# SmartPlantSensor.net
KiCad netlist of a schematic drawn in EAGLE
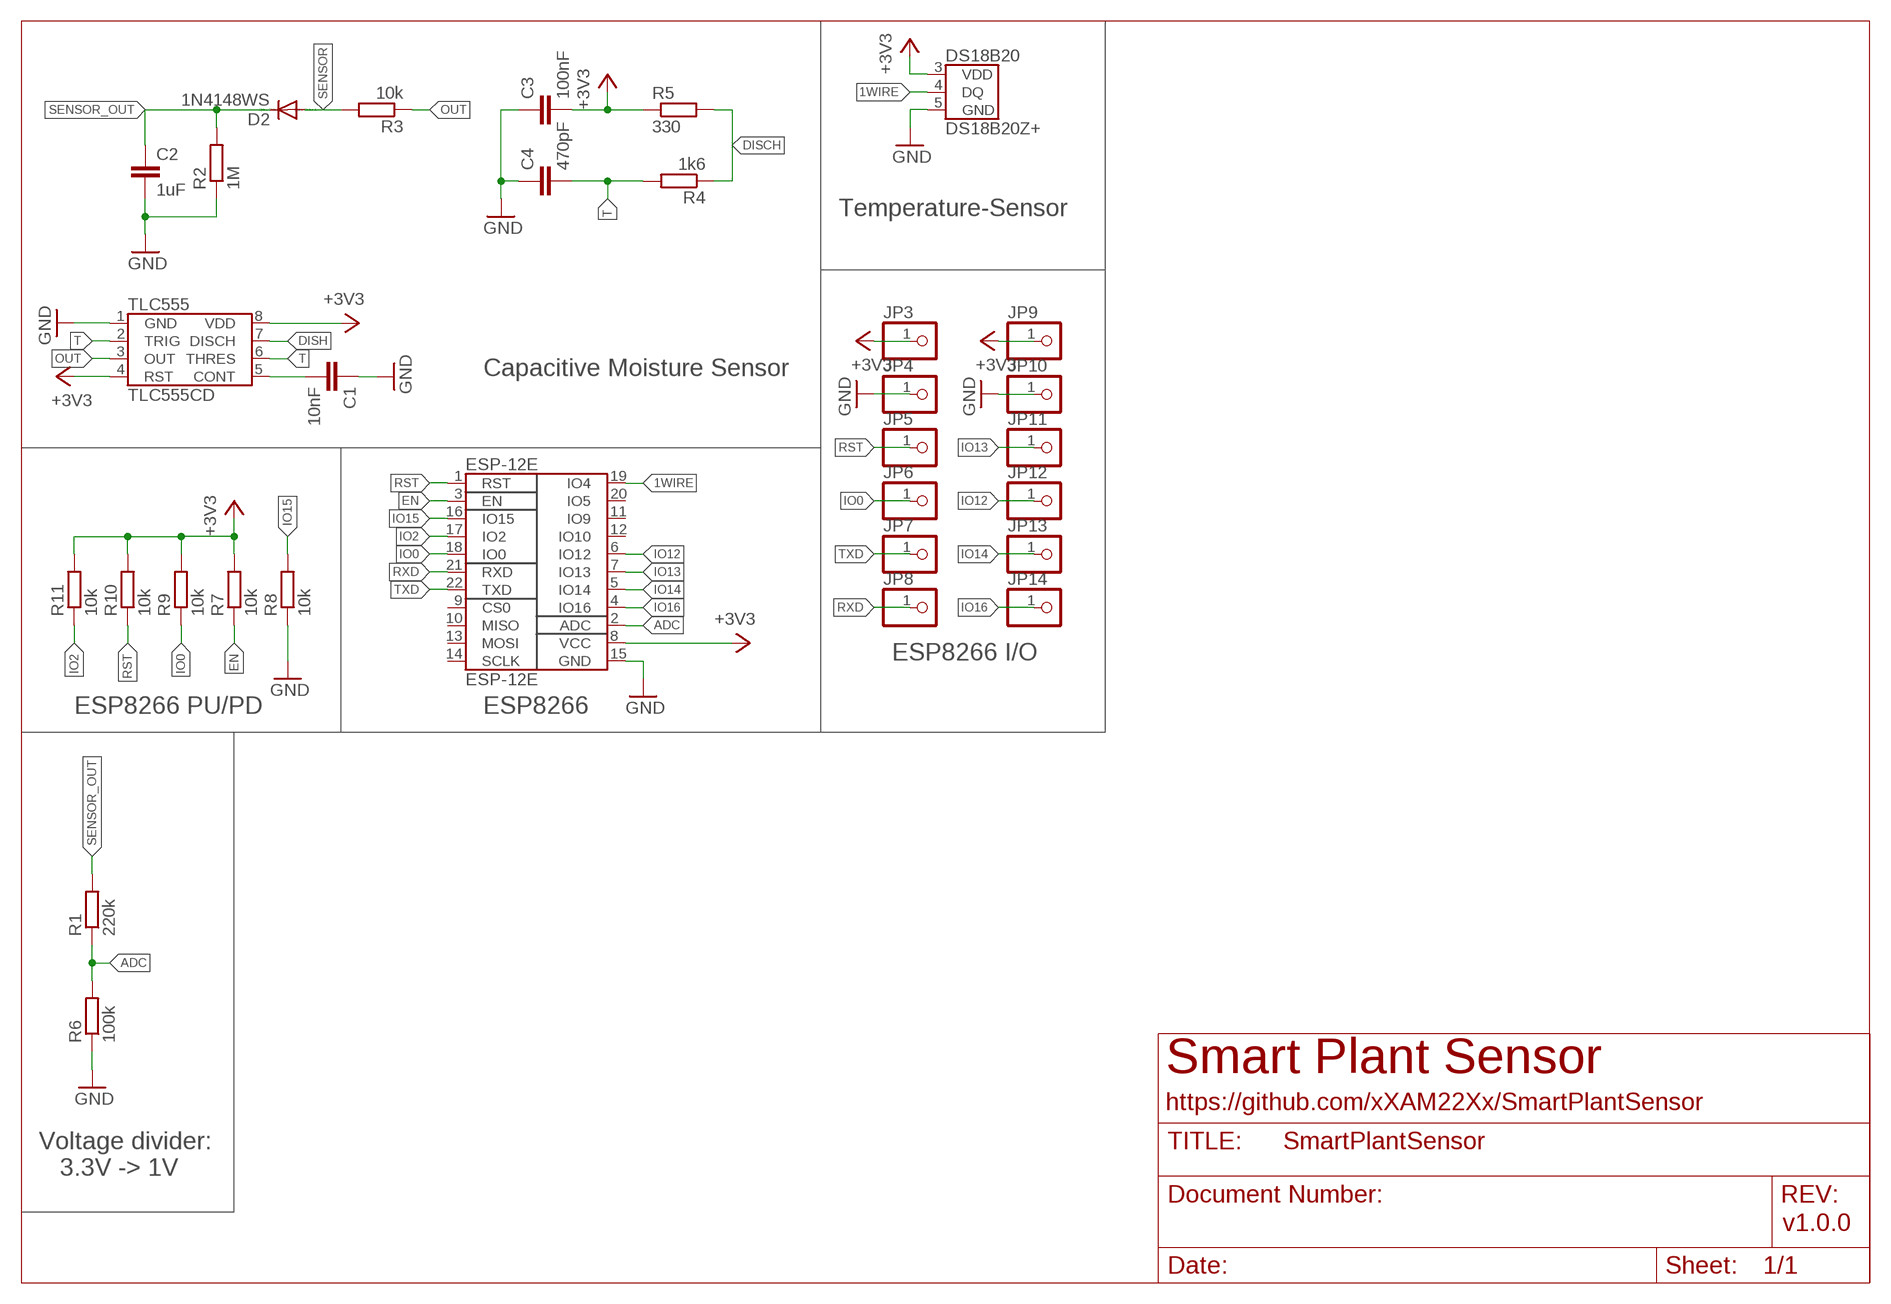
[diagram p0: schematic, sheet 1]

(export (version "E")
  (design (tool "Eeschema 10.0.6"))
  (components
    (comp (ref "C1")
      (value "10nF")
      (footprint "eagle-import:C0603")
      (libsource (lib "eagle-import") (part "C-EUC0603"))
    )
    (comp (ref "C2")
      (value "1uF")
      (footprint "eagle-import:C0603")
      (libsource (lib "eagle-import") (part "C-EUC0603"))
    )
    (comp (ref "C3")
      (value "100nF")
      (footprint "eagle-import:C0603")
      (libsource (lib "eagle-import") (part "C-EUC0603"))
    )
    (comp (ref "C4")
      (value "470pF")
      (footprint "eagle-import:C0603")
      (libsource (lib "eagle-import") (part "C-EUC0603"))
    )
    (comp (ref "D2")
      (value "1N4148WS")
      (footprint "eagle-import:SOD323-R")
      (libsource (lib "eagle-import") (part "DIODE-SOD323-R"))
    )
    (comp (ref "DS18B20")
      (value "DS18B20Z+")
      (footprint "eagle-import:SOIC8")
      (libsource (lib "eagle-import") (part "DS18B20Z+"))
    )
    (comp (ref "ESP-12E")
      (value "ESP-12E")
      (footprint "eagle-import:ESP-12E")
      (libsource (lib "eagle-import") (part "ESP-12E"))
    )
    (comp (ref "JP3")
      (value "PINHD-1X1")
      (footprint "eagle-import:1X01")
      (libsource (lib "eagle-import") (part "PINHD-1X1"))
    )
    (comp (ref "JP4")
      (value "PINHD-1X1")
      (footprint "eagle-import:1X01")
      (libsource (lib "eagle-import") (part "PINHD-1X1"))
    )
    (comp (ref "JP5")
      (value "PINHD-1X1")
      (footprint "eagle-import:1X01")
      (libsource (lib "eagle-import") (part "PINHD-1X1"))
    )
    (comp (ref "JP6")
      (value "PINHD-1X1")
      (footprint "eagle-import:1X01")
      (libsource (lib "eagle-import") (part "PINHD-1X1"))
    )
    (comp (ref "JP7")
      (value "PINHD-1X1")
      (footprint "eagle-import:1X01")
      (libsource (lib "eagle-import") (part "PINHD-1X1"))
    )
    (comp (ref "JP8")
      (value "PINHD-1X1")
      (footprint "eagle-import:1X01")
      (libsource (lib "eagle-import") (part "PINHD-1X1"))
    )
    (comp (ref "JP9")
      (value "PINHD-1X1")
      (footprint "eagle-import:1X01")
      (libsource (lib "eagle-import") (part "PINHD-1X1"))
    )
    (comp (ref "JP10")
      (value "PINHD-1X1")
      (footprint "eagle-import:1X01")
      (libsource (lib "eagle-import") (part "PINHD-1X1"))
    )
    (comp (ref "JP11")
      (value "PINHD-1X1")
      (footprint "eagle-import:1X01")
      (libsource (lib "eagle-import") (part "PINHD-1X1"))
    )
    (comp (ref "JP12")
      (value "PINHD-1X1")
      (footprint "eagle-import:1X01")
      (libsource (lib "eagle-import") (part "PINHD-1X1"))
    )
    (comp (ref "JP13")
      (value "PINHD-1X1")
      (footprint "eagle-import:1X01")
      (libsource (lib "eagle-import") (part "PINHD-1X1"))
    )
    (comp (ref "JP14")
      (value "PINHD-1X1")
      (footprint "eagle-import:1X01")
      (libsource (lib "eagle-import") (part "PINHD-1X1"))
    )
    (comp (ref "R1")
      (value "220k")
      (footprint "eagle-import:R0603")
      (libsource (lib "eagle-import") (part "R-EU_R0603"))
    )
    (comp (ref "R2")
      (value "1M")
      (footprint "eagle-import:R0603")
      (libsource (lib "eagle-import") (part "R-EU_R0603"))
    )
    (comp (ref "R3")
      (value "10k")
      (footprint "eagle-import:R0603")
      (libsource (lib "eagle-import") (part "R-EU_R0603"))
    )
    (comp (ref "R4")
      (value "1k6")
      (footprint "eagle-import:R0603")
      (libsource (lib "eagle-import") (part "R-EU_R0603"))
    )
    (comp (ref "R5")
      (value "330")
      (footprint "eagle-import:R0603")
      (libsource (lib "eagle-import") (part "R-EU_R0603"))
    )
    (comp (ref "R6")
      (value "100k")
      (footprint "eagle-import:R0603")
      (libsource (lib "eagle-import") (part "R-EU_R0603"))
    )
    (comp (ref "R7")
      (value "10k")
      (footprint "eagle-import:R0603")
      (libsource (lib "eagle-import") (part "R-EU_R0603"))
    )
    (comp (ref "R8")
      (value "10k")
      (footprint "eagle-import:R0603")
      (libsource (lib "eagle-import") (part "R-EU_R0603"))
    )
    (comp (ref "R9")
      (value "10k")
      (footprint "eagle-import:R0603")
      (libsource (lib "eagle-import") (part "R-EU_R0603"))
    )
    (comp (ref "R10")
      (value "10k")
      (footprint "eagle-import:R0603")
      (libsource (lib "eagle-import") (part "R-EU_R0603"))
    )
    (comp (ref "R11")
      (value "10k")
      (footprint "eagle-import:R0603")
      (libsource (lib "eagle-import") (part "R-EU_R0603"))
    )
    (comp (ref "TLC555")
      (value "TLC555CD")
      (footprint "eagle-import:SOIC8")
      (libsource (lib "eagle-import") (part "TLC555CD"))
    )
  )
  (nets
    (net (code "1") (name "+3V3") (class "Default")
      (node (ref "C3") (pin "2") (pinfunction "2_2") (pintype "passive"))
      (node (ref "DS18B20") (pin "3") (pinfunction "VDD_3") (pintype "bidirectional"))
      (node (ref "ESP-12E") (pin "8") (pinfunction "VCC_8") (pintype "bidirectional"))
      (node (ref "JP3") (pin "1") (pinfunction "1_1") (pintype "passive"))
      (node (ref "JP9") (pin "1") (pinfunction "1_1") (pintype "passive"))
      (node (ref "R10") (pin "2") (pinfunction "2_2") (pintype "passive"))
      (node (ref "R11") (pin "2") (pinfunction "2_2") (pintype "passive"))
      (node (ref "R5") (pin "1") (pinfunction "1_1") (pintype "passive"))
      (node (ref "R7") (pin "2") (pinfunction "2_2") (pintype "passive"))
      (node (ref "R9") (pin "2") (pinfunction "2_2") (pintype "passive"))
      (node (ref "TLC555") (pin "4") (pinfunction "RST_4") (pintype "bidirectional"))
      (node (ref "TLC555") (pin "8") (pinfunction "VDD_8") (pintype "bidirectional"))
    )
    (net (code "2") (name "1WIRE") (class "Default")
      (node (ref "DS18B20") (pin "4") (pinfunction "DQ_4") (pintype "bidirectional"))
      (node (ref "ESP-12E") (pin "19") (pinfunction "IO4_19") (pintype "bidirectional"))
    )
    (net (code "3") (name "ADC") (class "Default")
      (node (ref "ESP-12E") (pin "2") (pinfunction "ADC_2") (pintype "bidirectional"))
      (node (ref "R1") (pin "1") (pinfunction "1_1") (pintype "passive"))
      (node (ref "R6") (pin "2") (pinfunction "2_2") (pintype "passive"))
    )
    (net (code "4") (name "DISCH") (class "Default")
      (node (ref "R4") (pin "1") (pinfunction "1_1") (pintype "passive"))
      (node (ref "R5") (pin "2") (pinfunction "2_2") (pintype "passive"))
    )
    (net (code "5") (name "DISH") (class "Default")
      (node (ref "TLC555") (pin "7") (pinfunction "DISCH_7") (pintype "bidirectional"))
    )
    (net (code "6") (name "EN") (class "Default")
      (node (ref "ESP-12E") (pin "3") (pinfunction "EN_3") (pintype "bidirectional"))
      (node (ref "R7") (pin "1") (pinfunction "1_1") (pintype "passive"))
    )
    (net (code "7") (name "GND") (class "Default")
      (node (ref "C1") (pin "1") (pinfunction "1_1") (pintype "passive"))
      (node (ref "C2") (pin "2") (pinfunction "2_2") (pintype "passive"))
      (node (ref "C3") (pin "1") (pinfunction "1_1") (pintype "passive"))
      (node (ref "C4") (pin "1") (pinfunction "1_1") (pintype "passive"))
      (node (ref "DS18B20") (pin "5") (pinfunction "GND_5") (pintype "bidirectional"))
      (node (ref "ESP-12E") (pin "15") (pinfunction "GND_15") (pintype "bidirectional"))
      (node (ref "JP10") (pin "1") (pinfunction "1_1") (pintype "passive"))
      (node (ref "JP4") (pin "1") (pinfunction "1_1") (pintype "passive"))
      (node (ref "R2") (pin "1") (pinfunction "1_1") (pintype "passive"))
      (node (ref "R6") (pin "1") (pinfunction "1_1") (pintype "passive"))
      (node (ref "R8") (pin "1") (pinfunction "1_1") (pintype "passive"))
      (node (ref "TLC555") (pin "1") (pinfunction "GND_1") (pintype "bidirectional"))
    )
    (net (code "8") (name "IO0") (class "Default")
      (node (ref "ESP-12E") (pin "18") (pinfunction "IO0_18") (pintype "bidirectional"))
      (node (ref "JP6") (pin "1") (pinfunction "1_1") (pintype "passive"))
      (node (ref "R9") (pin "1") (pinfunction "1_1") (pintype "passive"))
    )
    (net (code "9") (name "IO2") (class "Default")
      (node (ref "ESP-12E") (pin "17") (pinfunction "IO2_17") (pintype "bidirectional"))
      (node (ref "R11") (pin "1") (pinfunction "1_1") (pintype "passive"))
    )
    (net (code "10") (name "IO12") (class "Default")
      (node (ref "ESP-12E") (pin "6") (pinfunction "IO12_6") (pintype "bidirectional"))
      (node (ref "JP12") (pin "1") (pinfunction "1_1") (pintype "passive"))
    )
    (net (code "11") (name "IO13") (class "Default")
      (node (ref "ESP-12E") (pin "7") (pinfunction "IO13_7") (pintype "bidirectional"))
      (node (ref "JP11") (pin "1") (pinfunction "1_1") (pintype "passive"))
    )
    (net (code "12") (name "IO14") (class "Default")
      (node (ref "ESP-12E") (pin "5") (pinfunction "IO14_5") (pintype "bidirectional"))
      (node (ref "JP13") (pin "1") (pinfunction "1_1") (pintype "passive"))
    )
    (net (code "13") (name "IO15") (class "Default")
      (node (ref "ESP-12E") (pin "16") (pinfunction "IO15_16") (pintype "bidirectional"))
      (node (ref "R8") (pin "2") (pinfunction "2_2") (pintype "passive"))
    )
    (net (code "14") (name "IO16") (class "Default")
      (node (ref "ESP-12E") (pin "4") (pinfunction "IO16_4") (pintype "bidirectional"))
      (node (ref "JP14") (pin "1") (pinfunction "1_1") (pintype "passive"))
    )
    (net (code "15") (name "Net-(TLC555-CONT)") (class "Default")
      (node (ref "C1") (pin "2") (pinfunction "2_2") (pintype "passive"))
      (node (ref "TLC555") (pin "5") (pinfunction "CONT_5") (pintype "bidirectional"))
    )
    (net (code "16") (name "OUT") (class "Default")
      (node (ref "R3") (pin "1") (pinfunction "1_1") (pintype "passive"))
      (node (ref "TLC555") (pin "3") (pinfunction "OUT_3") (pintype "bidirectional"))
    )
    (net (code "17") (name "RST") (class "Default")
      (node (ref "ESP-12E") (pin "1") (pinfunction "RST_1") (pintype "bidirectional"))
      (node (ref "JP5") (pin "1") (pinfunction "1_1") (pintype "passive"))
      (node (ref "R10") (pin "1") (pinfunction "1_1") (pintype "passive"))
    )
    (net (code "18") (name "RXD") (class "Default")
      (node (ref "ESP-12E") (pin "21") (pinfunction "RXD_21") (pintype "bidirectional"))
      (node (ref "JP8") (pin "1") (pinfunction "1_1") (pintype "passive"))
    )
    (net (code "19") (name "SENSOR") (class "Default")
      (node (ref "D2") (pin "A") (pinfunction "A_A") (pintype "passive"))
      (node (ref "R3") (pin "2") (pinfunction "2_2") (pintype "passive"))
    )
    (net (code "20") (name "SENSOR_OUT") (class "Default")
      (node (ref "C2") (pin "1") (pinfunction "1_1") (pintype "passive"))
      (node (ref "D2") (pin "C") (pinfunction "C_C") (pintype "passive"))
      (node (ref "R1") (pin "2") (pinfunction "2_2") (pintype "passive"))
      (node (ref "R2") (pin "2") (pinfunction "2_2") (pintype "passive"))
    )
    (net (code "21") (name "T") (class "Default")
      (node (ref "C4") (pin "2") (pinfunction "2_2") (pintype "passive"))
      (node (ref "R4") (pin "2") (pinfunction "2_2") (pintype "passive"))
      (node (ref "TLC555") (pin "2") (pinfunction "TRIG_2") (pintype "bidirectional"))
      (node (ref "TLC555") (pin "6") (pinfunction "THRES_6") (pintype "bidirectional"))
    )
    (net (code "22") (name "TXD") (class "Default")
      (node (ref "ESP-12E") (pin "22") (pinfunction "TXD_22") (pintype "bidirectional"))
      (node (ref "JP7") (pin "1") (pinfunction "1_1") (pintype "passive"))
    )
    (net (code "23") (name "unconnected-(ESP-12E-CS0-Pad9)") (class "Default")
      (node (ref "ESP-12E") (pin "9") (pinfunction "CS0_9") (pintype "bidirectional"))
    )
    (net (code "24") (name "unconnected-(ESP-12E-IO5-Pad20)") (class "Default")
      (node (ref "ESP-12E") (pin "20") (pinfunction "IO5_20") (pintype "bidirectional"))
    )
    (net (code "25") (name "unconnected-(ESP-12E-IO9-Pad11)") (class "Default")
      (node (ref "ESP-12E") (pin "11") (pinfunction "IO9_11") (pintype "bidirectional"))
    )
    (net (code "26") (name "unconnected-(ESP-12E-IO10-Pad12)") (class "Default")
      (node (ref "ESP-12E") (pin "12") (pinfunction "IO10_12") (pintype "bidirectional"))
    )
    (net (code "27") (name "unconnected-(ESP-12E-MISO-Pad10)") (class "Default")
      (node (ref "ESP-12E") (pin "10") (pinfunction "MISO_10") (pintype "bidirectional"))
    )
    (net (code "28") (name "unconnected-(ESP-12E-MOSI-Pad13)") (class "Default")
      (node (ref "ESP-12E") (pin "13") (pinfunction "MOSI_13") (pintype "bidirectional"))
    )
    (net (code "29") (name "unconnected-(ESP-12E-SCLK-Pad14)") (class "Default")
      (node (ref "ESP-12E") (pin "14") (pinfunction "SCLK_14") (pintype "bidirectional"))
    )
  )
)
